# secondary_EEPROM_and_T.net
KiCad netlist of a schematic drawn in Altium Designer
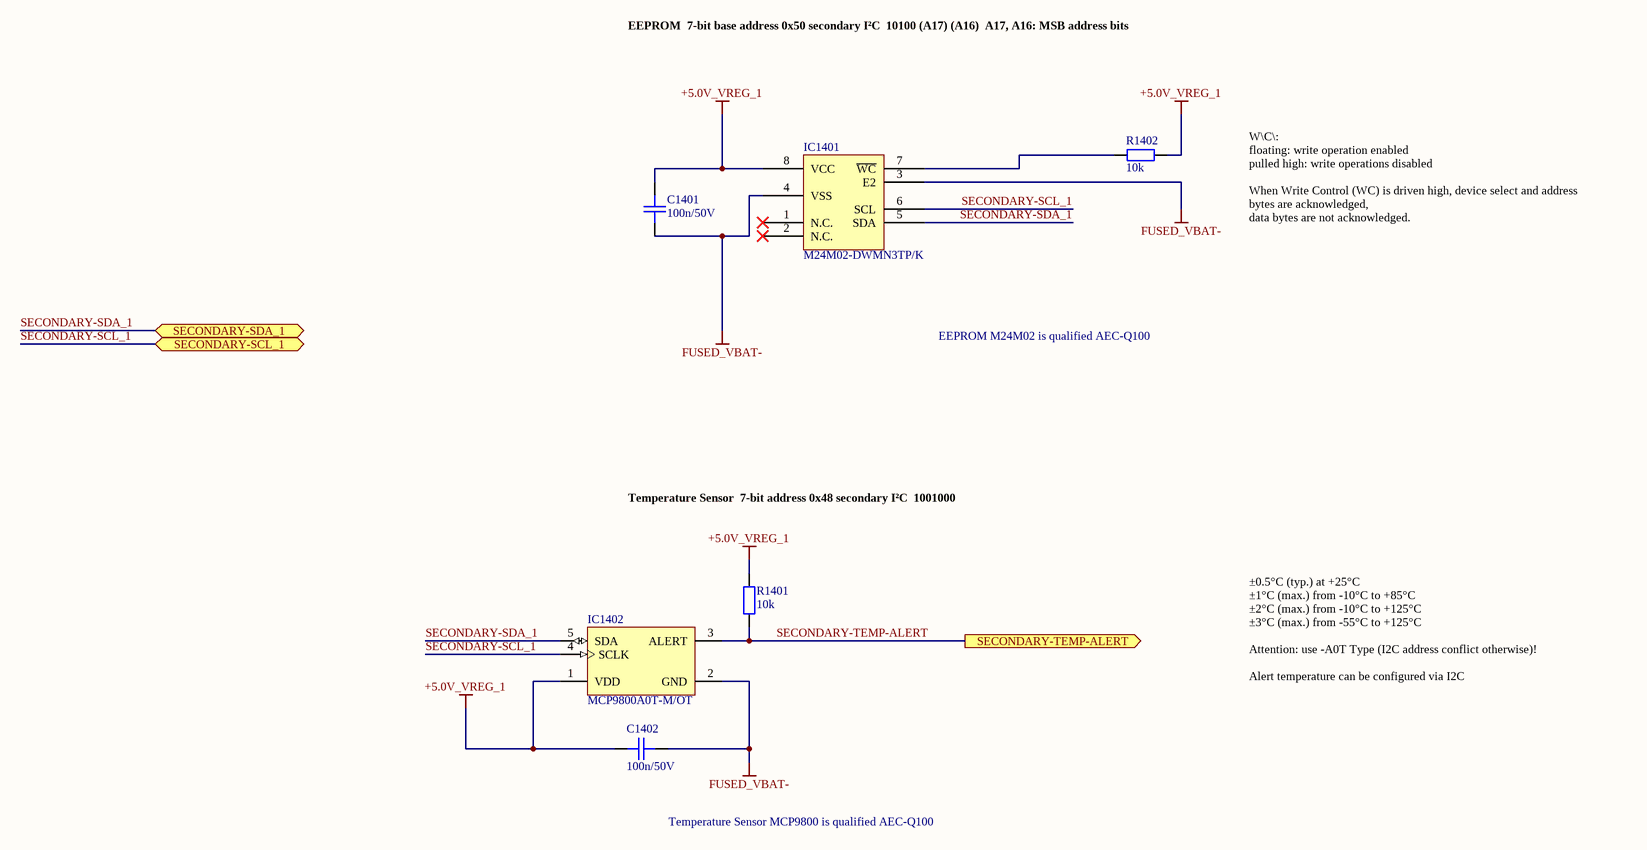
[diagram p0: secondary_EEPROM_and_T.SchDoc]

(export (version "E")
  (design (tool "Eeschema 10.0.6"))
  (components
    (comp (ref "C1401")
      (value "100n/50V")
      (footprint "CAPC1608X08N")
      (description "MLCC")
      (fields (field (name "PART NUMBER") "gen_C_ceramic_100n_50V_X7R_0603"))
      (libsource (lib "OE750") (part "C"))
    )
    (comp (ref "C1402")
      (value "100n/50V")
      (footprint "CAPC1608X08N")
      (description "MLCC")
      (fields (field (name "PART NUMBER") "gen_C_ceramic_100n_50V_X7R_0603"))
      (libsource (lib "OE750") (part "C"))
    )
    (comp (ref "IC1401")
      (value "M24M02-DWMN3TP/K")
      (footprint "SOIC127P600X175-8N")
      (description "Automotive 2-Mbit serial I²C \r\nbus EEPROM with 1 MHz clock")
      (fields (field (name "MANUFACTURER") "STMicroelectronics"))
      (libsource (lib "OE750") (part "M24M02-DWMN3TP/K"))
    )
    (comp (ref "IC1402")
      (value "MCP9800A0T-M/OT")
      (footprint "SOT-23-OT5_L")
      (libsource (lib "Altium Content Vault") (part "SEN-TEMP-MCP980X-5"))
    )
    (comp (ref "R1401")
      (value "10k")
      (footprint "RESC1608X05N")
      (description "SMD Resistor 10k 0603")
      (fields (field (name "PART NUMBER") "gen_R_10k_0603") (field (name "TOLERANCE") "1%"))
      (libsource (lib "OE750") (part "R"))
    )
    (comp (ref "R1402")
      (value "10k")
      (footprint "RESC1608X05N")
      (description "SMD Resistor 10k 0603")
      (fields (field (name "PART NUMBER") "gen_R_10k_0603") (field (name "TOLERANCE") "1%"))
      (libsource (lib "OE750") (part "R"))
    )
  )
  (nets
    (net (code "1") (name "+5.0V_VREG_1") (class "Default")
      (node (ref "C1401") (pin "2") (pinfunction "2_2") (pintype "passive"))
      (node (ref "C1402") (pin "2") (pinfunction "2_2") (pintype "passive"))
      (node (ref "IC1401") (pin "8") (pinfunction "VCC_8") (pintype "power_in"))
      (node (ref "IC1402") (pin "1") (pinfunction "VDD_1") (pintype "power_in"))
      (node (ref "R1401") (pin "2") (pinfunction "2_2") (pintype "passive"))
      (node (ref "R1402") (pin "2") (pinfunction "2_2") (pintype "passive"))
    )
    (net (code "2") (name "/SECONDARY-SCL_1") (class "Default")
      (node (ref "IC1401") (pin "6") (pinfunction "SCL_6") (pintype "passive"))
      (node (ref "IC1402") (pin "4") (pinfunction "SCLK_4") (pintype "input"))
    )
    (net (code "3") (name "/SECONDARY-SDA_1") (class "Default")
      (node (ref "IC1401") (pin "5") (pinfunction "SDA_5") (pintype "passive"))
      (node (ref "IC1402") (pin "5") (pinfunction "SDA_5") (pintype "bidirectional"))
    )
    (net (code "4") (name "/SECONDARY-TEMP-ALERT") (class "Default")
      (node (ref "IC1402") (pin "3") (pinfunction "ALERT_3") (pintype "open_collector"))
      (node (ref "R1401") (pin "1") (pinfunction "1_1") (pintype "passive"))
    )
    (net (code "5") (name "FUSED_VBAT-") (class "Default")
      (node (ref "C1401") (pin "1") (pinfunction "1_1") (pintype "passive"))
      (node (ref "C1402") (pin "1") (pinfunction "1_1") (pintype "passive"))
      (node (ref "IC1401") (pin "3") (pinfunction "E2_3") (pintype "passive"))
      (node (ref "IC1401") (pin "4") (pinfunction "VSS_4") (pintype "power_in"))
      (node (ref "IC1402") (pin "2") (pinfunction "GND_2") (pintype "power_in"))
    )
    (net (code "6") (name "Net-(IC1401-~{WC})") (class "Default")
      (node (ref "IC1401") (pin "7") (pinfunction "~{WC}_7") (pintype "passive"))
      (node (ref "R1402") (pin "1") (pinfunction "1_1") (pintype "passive"))
    )
    (net (code "7") (name "unconnected-(IC1401-N.C.-Pad1)") (class "Default")
      (node (ref "IC1401") (pin "1") (pinfunction "N.C._1") (pintype "passive+no_connect"))
    )
    (net (code "8") (name "unconnected-(IC1401-N.C.-Pad2)") (class "Default")
      (node (ref "IC1401") (pin "2") (pinfunction "N.C._2") (pintype "passive+no_connect"))
    )
  )
)
